# Acti_champ_cable.net
KiCad netlist of a schematic drawn in EAGLE
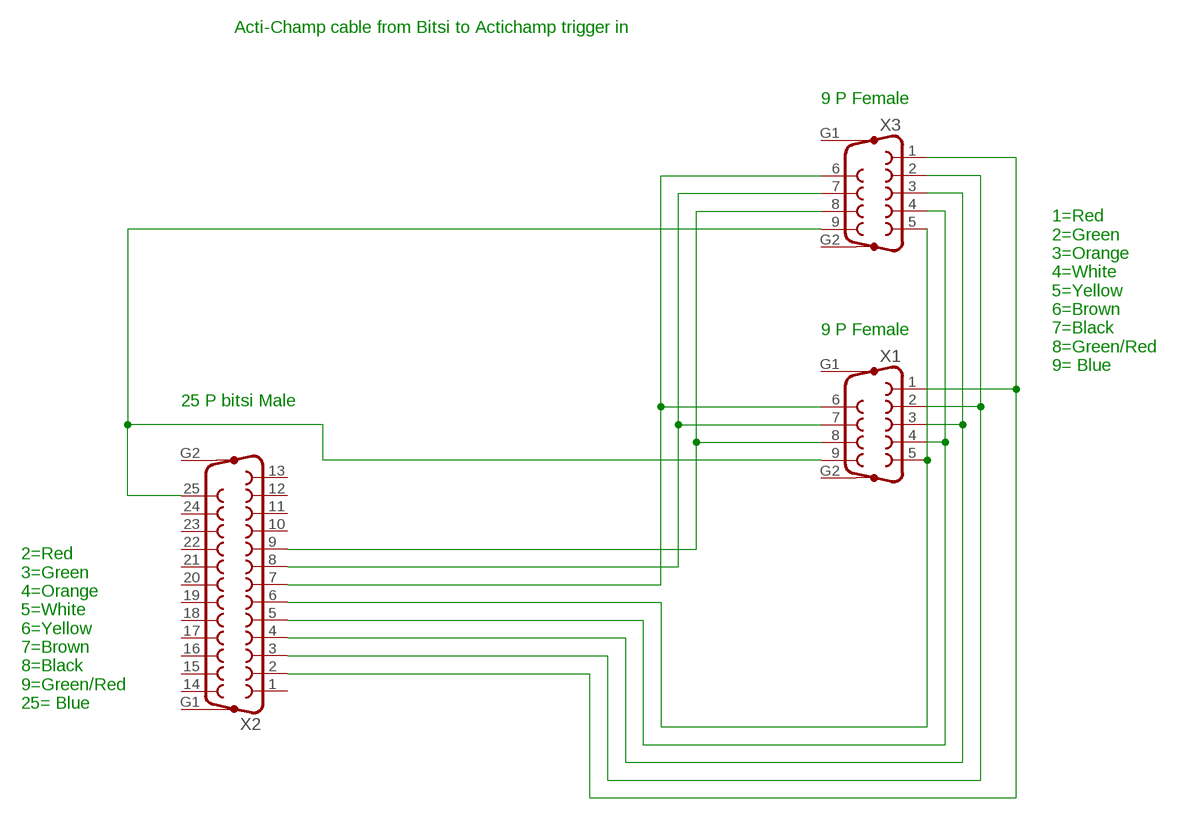
[diagram p0: schematic, sheet 1]

(export (version "E")
  (design (tool "Eeschema 10.0.6"))
  (components
    (comp (ref "X1")
      (value "F09HP")
      (footprint "eagle-import:F09HP")
      (libsource (lib "eagle-import") (part "F09HP"))
    )
    (comp (ref "X2")
      (value "F25HP")
      (footprint "eagle-import:F25HP")
      (libsource (lib "eagle-import") (part "F25HP"))
    )
    (comp (ref "X3")
      (value "F09HP")
      (footprint "eagle-import:F09HP")
      (libsource (lib "eagle-import") (part "F09HP"))
    )
  )
  (nets
    (net (code "1") (name "Net-(X1-Pad1)") (class "Default")
      (node (ref "X1") (pin "1") (pinfunction "1_1") (pintype "passive"))
      (node (ref "X2") (pin "2") (pinfunction "2_2") (pintype "passive"))
      (node (ref "X3") (pin "1") (pinfunction "1_1") (pintype "passive"))
    )
    (net (code "2") (name "Net-(X1-Pad2)") (class "Default")
      (node (ref "X1") (pin "2") (pinfunction "2_2") (pintype "passive"))
      (node (ref "X2") (pin "3") (pinfunction "3_3") (pintype "passive"))
      (node (ref "X3") (pin "2") (pinfunction "2_2") (pintype "passive"))
    )
    (net (code "3") (name "Net-(X1-Pad3)") (class "Default")
      (node (ref "X1") (pin "3") (pinfunction "3_3") (pintype "passive"))
      (node (ref "X2") (pin "4") (pinfunction "4_4") (pintype "passive"))
      (node (ref "X3") (pin "3") (pinfunction "3_3") (pintype "passive"))
    )
    (net (code "4") (name "Net-(X1-Pad4)") (class "Default")
      (node (ref "X1") (pin "4") (pinfunction "4_4") (pintype "passive"))
      (node (ref "X2") (pin "5") (pinfunction "5_5") (pintype "passive"))
      (node (ref "X3") (pin "4") (pinfunction "4_4") (pintype "passive"))
    )
    (net (code "5") (name "Net-(X1-Pad5)") (class "Default")
      (node (ref "X1") (pin "5") (pinfunction "5_5") (pintype "passive"))
      (node (ref "X2") (pin "6") (pinfunction "6_6") (pintype "passive"))
      (node (ref "X3") (pin "5") (pinfunction "5_5") (pintype "passive"))
    )
    (net (code "6") (name "Net-(X1-Pad6)") (class "Default")
      (node (ref "X1") (pin "6") (pinfunction "6_6") (pintype "passive"))
      (node (ref "X2") (pin "7") (pinfunction "7_7") (pintype "passive"))
      (node (ref "X3") (pin "6") (pinfunction "6_6") (pintype "passive"))
    )
    (net (code "7") (name "Net-(X1-Pad7)") (class "Default")
      (node (ref "X1") (pin "7") (pinfunction "7_7") (pintype "passive"))
      (node (ref "X2") (pin "8") (pinfunction "8_8") (pintype "passive"))
      (node (ref "X3") (pin "7") (pinfunction "7_7") (pintype "passive"))
    )
    (net (code "8") (name "Net-(X1-Pad8)") (class "Default")
      (node (ref "X1") (pin "8") (pinfunction "8_8") (pintype "passive"))
      (node (ref "X2") (pin "9") (pinfunction "9_9") (pintype "passive"))
      (node (ref "X3") (pin "8") (pinfunction "8_8") (pintype "passive"))
    )
    (net (code "9") (name "Net-(X1-Pad9)") (class "Default")
      (node (ref "X1") (pin "9") (pinfunction "9_9") (pintype "passive"))
      (node (ref "X2") (pin "25") (pinfunction "25_25") (pintype "passive"))
      (node (ref "X3") (pin "9") (pinfunction "9_9") (pintype "passive"))
    )
    (net (code "10") (name "unconnected-(X1-PadG1)") (class "Default")
      (node (ref "X1") (pin "G1") (pinfunction "G1_G1") (pintype "passive"))
    )
    (net (code "11") (name "unconnected-(X1-PadG2)") (class "Default")
      (node (ref "X1") (pin "G2") (pinfunction "G2_G2") (pintype "passive"))
    )
    (net (code "12") (name "unconnected-(X2-Pad1)") (class "Default")
      (node (ref "X2") (pin "1") (pinfunction "1_1") (pintype "passive"))
    )
    (net (code "13") (name "unconnected-(X2-Pad10)") (class "Default")
      (node (ref "X2") (pin "10") (pinfunction "10_10") (pintype "passive"))
    )
    (net (code "14") (name "unconnected-(X2-Pad11)") (class "Default")
      (node (ref "X2") (pin "11") (pinfunction "11_11") (pintype "passive"))
    )
    (net (code "15") (name "unconnected-(X2-Pad12)") (class "Default")
      (node (ref "X2") (pin "12") (pinfunction "12_12") (pintype "passive"))
    )
    (net (code "16") (name "unconnected-(X2-Pad13)") (class "Default")
      (node (ref "X2") (pin "13") (pinfunction "13_13") (pintype "passive"))
    )
    (net (code "17") (name "unconnected-(X2-Pad14)") (class "Default")
      (node (ref "X2") (pin "14") (pinfunction "14_14") (pintype "passive"))
    )
    (net (code "18") (name "unconnected-(X2-Pad15)") (class "Default")
      (node (ref "X2") (pin "15") (pinfunction "15_15") (pintype "passive"))
    )
    (net (code "19") (name "unconnected-(X2-Pad16)") (class "Default")
      (node (ref "X2") (pin "16") (pinfunction "16_16") (pintype "passive"))
    )
    (net (code "20") (name "unconnected-(X2-Pad17)") (class "Default")
      (node (ref "X2") (pin "17") (pinfunction "17_17") (pintype "passive"))
    )
    (net (code "21") (name "unconnected-(X2-Pad18)") (class "Default")
      (node (ref "X2") (pin "18") (pinfunction "18_18") (pintype "passive"))
    )
    (net (code "22") (name "unconnected-(X2-Pad19)") (class "Default")
      (node (ref "X2") (pin "19") (pinfunction "19_19") (pintype "passive"))
    )
    (net (code "23") (name "unconnected-(X2-Pad20)") (class "Default")
      (node (ref "X2") (pin "20") (pinfunction "20_20") (pintype "passive"))
    )
    (net (code "24") (name "unconnected-(X2-Pad21)") (class "Default")
      (node (ref "X2") (pin "21") (pinfunction "21_21") (pintype "passive"))
    )
    (net (code "25") (name "unconnected-(X2-Pad22)") (class "Default")
      (node (ref "X2") (pin "22") (pinfunction "22_22") (pintype "passive"))
    )
    (net (code "26") (name "unconnected-(X2-Pad23)") (class "Default")
      (node (ref "X2") (pin "23") (pinfunction "23_23") (pintype "passive"))
    )
    (net (code "27") (name "unconnected-(X2-Pad24)") (class "Default")
      (node (ref "X2") (pin "24") (pinfunction "24_24") (pintype "passive"))
    )
    (net (code "28") (name "unconnected-(X2-PadG1)") (class "Default")
      (node (ref "X2") (pin "G1") (pinfunction "G1_G1") (pintype "passive"))
    )
    (net (code "29") (name "unconnected-(X2-PadG2)") (class "Default")
      (node (ref "X2") (pin "G2") (pinfunction "G2_G2") (pintype "passive"))
    )
    (net (code "30") (name "unconnected-(X3-PadG1)") (class "Default")
      (node (ref "X3") (pin "G1") (pinfunction "G1_G1") (pintype "passive"))
    )
    (net (code "31") (name "unconnected-(X3-PadG2)") (class "Default")
      (node (ref "X3") (pin "G2") (pinfunction "G2_G2") (pintype "passive"))
    )
  )
)
